# LPCB218_-_CHARGER_INTERFACE.net
KiCad netlist of a schematic drawn in Altium Designer
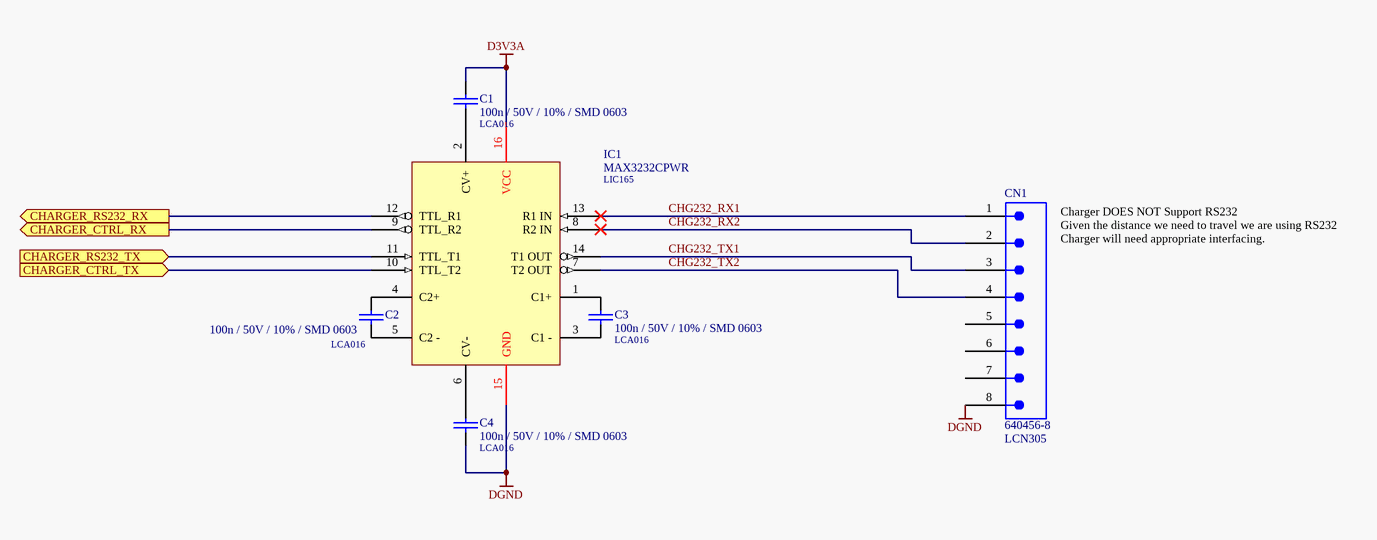
[diagram p0: LPCB218 - CHARGER INTERFACE.SchDoc]

(export (version "E")
  (design (tool "Eeschema 10.0.6"))
  (components
    (comp (ref "C1")
      (value "100n / 50V / 10% / SMD 0603")
      (footprint "LFP011__CC1608-0603-IPC7351_B")
      (description "Capacitor, Ceramic Chip, 100nF, 50V, 10%, SMD 0603")
      (fields (field (name "LDL_NUMBER") "LCA016"))
      (libsource (lib "LDL_Capacitors") (part "100n / 50V / 10% / SMD 0603"))
    )
    (comp (ref "C2")
      (value "100n / 50V / 10% / SMD 0603")
      (footprint "LFP011__CC1608-0603-IPC7351_B")
      (description "Capacitor, Ceramic Chip, 100nF, 50V, 10%, SMD 0603")
      (fields (field (name "LDL_NUMBER") "LCA016"))
      (libsource (lib "LDL_Capacitors") (part "100n / 50V / 10% / SMD 0603"))
    )
    (comp (ref "C3")
      (value "100n / 50V / 10% / SMD 0603")
      (footprint "LFP011__CC1608-0603-IPC7351_B")
      (description "Capacitor, Ceramic Chip, 100nF, 50V, 10%, SMD 0603")
      (fields (field (name "LDL_NUMBER") "LCA016"))
      (libsource (lib "LDL_Capacitors") (part "100n / 50V / 10% / SMD 0603"))
    )
    (comp (ref "C4")
      (value "100n / 50V / 10% / SMD 0603")
      (footprint "LFP011__CC1608-0603-IPC7351_B")
      (description "Capacitor, Ceramic Chip, 100nF, 50V, 10%, SMD 0603")
      (fields (field (name "LDL_NUMBER") "LCA016"))
      (libsource (lib "LDL_Capacitors") (part "100n / 50V / 10% / SMD 0603"))
    )
    (comp (ref "CN1")
      (value "640456-8")
      (footprint "640456-8")
      (description "Connector, Male Header, 8 Way")
      (fields (field (name "LDL_NUMBER") "LCN305"))
      (libsource (lib "LDL_Connectors") (part "640456-8"))
    )
    (comp (ref "IC1")
      (value "MAX3232CPWR")
      (footprint "LFP049__TSSOP-16")
      (description "IC, RS232 Line Driver, 3.3V, SMD TSSOP16")
      (fields (field (name "LDL_NUMBER") "LIC165"))
      (libsource (lib "LDL_Semiconductors") (part "MAX3232CPWR"))
    )
  )
  (nets
    (net (code "1") (name "/CHARGER_CTRL_RX") (class "Default")
      (node (ref "IC1") (pin "9") (pinfunction "TTL_R2_9") (pintype "output"))
    )
    (net (code "2") (name "/CHARGER_CTRL_TX") (class "Default")
      (node (ref "IC1") (pin "10") (pinfunction "TTL_T2_10") (pintype "input"))
    )
    (net (code "3") (name "/CHARGER_RS232_RX") (class "Default")
      (node (ref "IC1") (pin "12") (pinfunction "TTL_R1_12") (pintype "output"))
    )
    (net (code "4") (name "/CHARGER_RS232_TX") (class "Default")
      (node (ref "IC1") (pin "11") (pinfunction "TTL_T1_11") (pintype "input"))
    )
    (net (code "5") (name "/CHG232_RX1") (class "Default")
      (node (ref "CN1") (pin "1") (pinfunction "1_1") (pintype "passive"))
      (node (ref "IC1") (pin "13") (pinfunction "R1_IN_13") (pintype "input"))
    )
    (net (code "6") (name "/CHG232_RX2") (class "Default")
      (node (ref "CN1") (pin "2") (pinfunction "2_2") (pintype "passive"))
      (node (ref "IC1") (pin "8") (pinfunction "R2_IN_8") (pintype "input"))
    )
    (net (code "7") (name "/CHG232_TX1") (class "Default")
      (node (ref "CN1") (pin "3") (pinfunction "3_3") (pintype "passive"))
      (node (ref "IC1") (pin "14") (pinfunction "T1_OUT_14") (pintype "output"))
    )
    (net (code "8") (name "/CHG232_TX2") (class "Default")
      (node (ref "CN1") (pin "4") (pinfunction "4_4") (pintype "passive"))
      (node (ref "IC1") (pin "7") (pinfunction "T2_OUT_7") (pintype "output"))
    )
    (net (code "9") (name "D3V3A") (class "Default")
      (node (ref "C1") (pin "1") (pintype "passive"))
      (node (ref "IC1") (pin "16") (pinfunction "VCC_16") (pintype "power_in"))
    )
    (net (code "10") (name "DGND") (class "Default")
      (node (ref "C4") (pin "2") (pintype "passive"))
      (node (ref "CN1") (pin "8") (pinfunction "8_8") (pintype "passive"))
      (node (ref "IC1") (pin "15") (pinfunction "GND_15") (pintype "power_in"))
    )
    (net (code "11") (name "Net-(IC1-C1+)") (class "Default")
      (node (ref "C3") (pin "1") (pintype "passive"))
      (node (ref "IC1") (pin "1") (pinfunction "C1+_1") (pintype "passive"))
    )
    (net (code "12") (name "Net-(IC1-C1_-)") (class "Default")
      (node (ref "C3") (pin "2") (pintype "passive"))
      (node (ref "IC1") (pin "3") (pinfunction "C1_-_3") (pintype "passive"))
    )
    (net (code "13") (name "Net-(IC1-C2+)") (class "Default")
      (node (ref "C2") (pin "1") (pintype "passive"))
      (node (ref "IC1") (pin "4") (pinfunction "C2+_4") (pintype "passive"))
    )
    (net (code "14") (name "Net-(IC1-C2_-)") (class "Default")
      (node (ref "C2") (pin "2") (pintype "passive"))
      (node (ref "IC1") (pin "5") (pinfunction "C2_-_5") (pintype "passive"))
    )
    (net (code "15") (name "Net-(IC1-CV+)") (class "Default")
      (node (ref "C1") (pin "2") (pintype "passive"))
      (node (ref "IC1") (pin "2") (pinfunction "CV+_2") (pintype "passive"))
    )
    (net (code "16") (name "Net-(IC1-CV-)") (class "Default")
      (node (ref "C4") (pin "1") (pintype "passive"))
      (node (ref "IC1") (pin "6") (pinfunction "CV-_6") (pintype "passive"))
    )
    (net (code "17") (name "unconnected-(CN1-Pad5)") (class "Default")
      (node (ref "CN1") (pin "5") (pinfunction "5_5") (pintype "passive"))
    )
    (net (code "18") (name "unconnected-(CN1-Pad6)") (class "Default")
      (node (ref "CN1") (pin "6") (pinfunction "6_6") (pintype "passive"))
    )
    (net (code "19") (name "unconnected-(CN1-Pad7)") (class "Default")
      (node (ref "CN1") (pin "7") (pinfunction "7_7") (pintype "passive"))
    )
  )
)
